# GBox2-can_diy.net
KiCad netlist of a schematic drawn in EAGLE
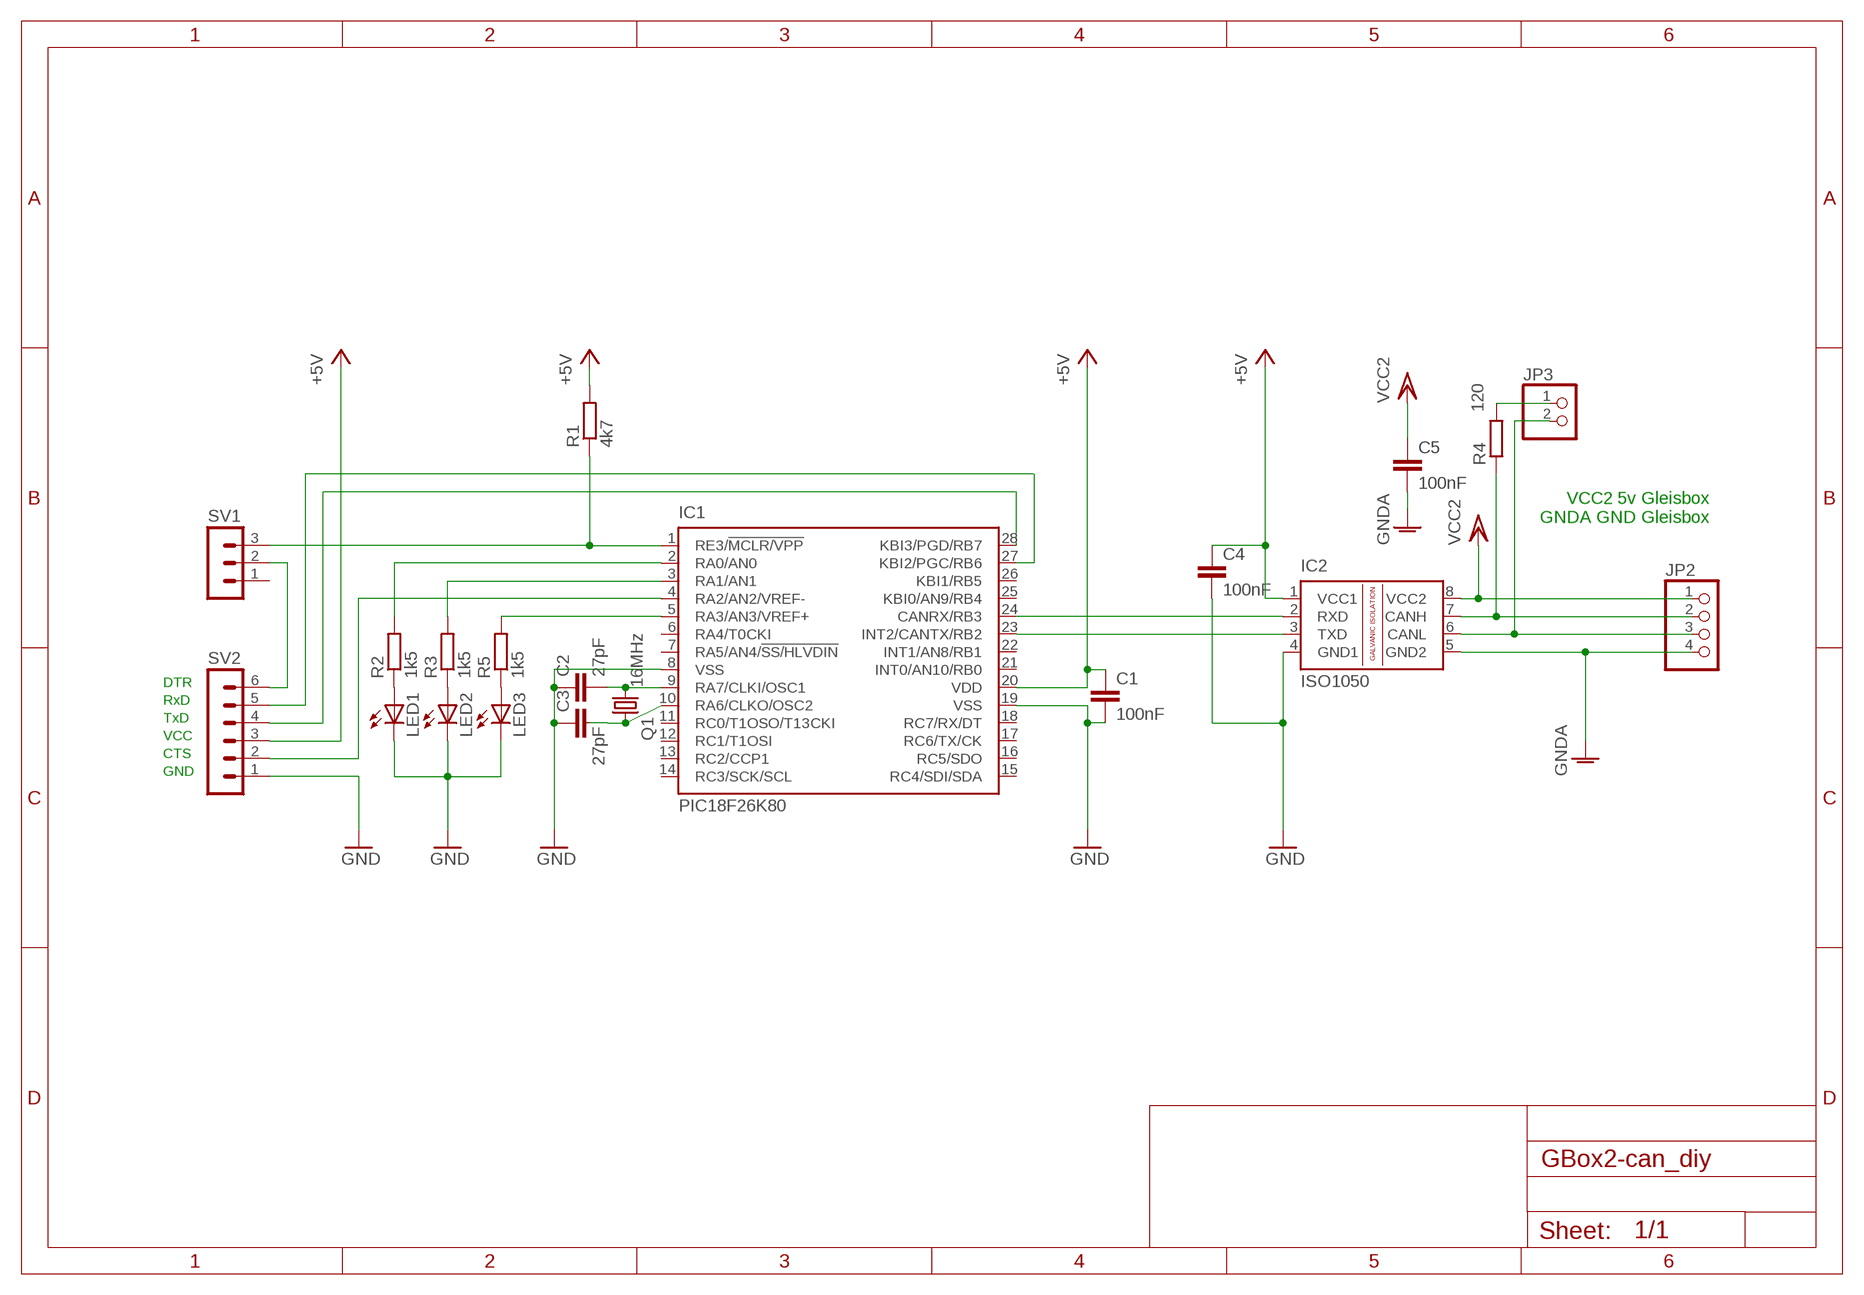
[diagram p0: schematic, sheet 1]

(export (version "E")
  (design (tool "Eeschema 10.0.6"))
  (components
    (comp (ref "C1")
      (value "100nF")
      (footprint "eagle-import:C1206")
      (libsource (lib "eagle-import") (part "C-EUC1206"))
    )
    (comp (ref "C2")
      (value "27pF")
      (footprint "eagle-import:C1206")
      (libsource (lib "eagle-import") (part "C-EUC1206"))
    )
    (comp (ref "C3")
      (value "27pF")
      (footprint "eagle-import:C1206")
      (libsource (lib "eagle-import") (part "C-EUC1206"))
    )
    (comp (ref "C4")
      (value "100nF")
      (footprint "eagle-import:C1206")
      (libsource (lib "eagle-import") (part "C-EUC1206"))
    )
    (comp (ref "C5")
      (value "100nF")
      (footprint "eagle-import:C1206")
      (libsource (lib "eagle-import") (part "C-EUC1206"))
    )
    (comp (ref "IC1")
      (value "PIC18F26K80")
      (footprint "eagle-import:SO28W")
      (libsource (lib "eagle-import") (part "PIC18F26K80-E/SO"))
    )
    (comp (ref "IC2")
      (value "ISO1050")
      (footprint "eagle-import:DUB-R-PDSO-G8")
      (fields (field (name "MPN") "ISO1050DUBR"))
      (libsource (lib "eagle-import") (part "ISO1050DUB"))
    )
    (comp (ref "JP2")
      (value "PINHD-1X4")
      (footprint "eagle-import:1X04")
      (libsource (lib "eagle-import") (part "PINHD-1X4"))
    )
    (comp (ref "JP3")
      (value "PINHD-1X2")
      (footprint "eagle-import:1X02")
      (libsource (lib "eagle-import") (part "PINHD-1X2"))
    )
    (comp (ref "LED1")
      (value "LEDSML1206")
      (footprint "eagle-import:SML1206")
      (libsource (lib "eagle-import") (part "LEDSML1206"))
    )
    (comp (ref "LED2")
      (value "LEDSML1206")
      (footprint "eagle-import:SML1206")
      (libsource (lib "eagle-import") (part "LEDSML1206"))
    )
    (comp (ref "LED3")
      (value "LEDSML1206")
      (footprint "eagle-import:SML1206")
      (libsource (lib "eagle-import") (part "LEDSML1206"))
    )
    (comp (ref "Q1")
      (value "16MHz")
      (footprint "eagle-import:HC49UP")
      (libsource (lib "eagle-import") (part "CRYSTALHC49UP"))
    )
    (comp (ref "R1")
      (value "4k7")
      (footprint "eagle-import:R1206")
      (libsource (lib "eagle-import") (part "R-EU_R1206"))
    )
    (comp (ref "R2")
      (value "1k5")
      (footprint "eagle-import:R1206")
      (libsource (lib "eagle-import") (part "R-EU_R1206"))
    )
    (comp (ref "R3")
      (value "1k5")
      (footprint "eagle-import:R1206")
      (libsource (lib "eagle-import") (part "R-EU_R1206"))
    )
    (comp (ref "R4")
      (value "120")
      (footprint "eagle-import:0204_7")
      (libsource (lib "eagle-import") (part "R-EU_0204/7"))
    )
    (comp (ref "R5")
      (value "1k5")
      (footprint "eagle-import:R1206")
      (libsource (lib "eagle-import") (part "R-EU_R1206"))
    )
    (comp (ref "SV1")
      (value "MA03-1")
      (footprint "eagle-import:MA03-1")
      (libsource (lib "eagle-import") (part "MA03-1"))
    )
    (comp (ref "SV2")
      (value "MA06-1")
      (footprint "eagle-import:MA06-1")
      (libsource (lib "eagle-import") (part "MA06-1"))
    )
  )
  (nets
    (net (code "1") (name "+5V") (class "Default")
      (node (ref "C1") (pin "1") (pinfunction "1_1") (pintype "passive"))
      (node (ref "C4") (pin "1") (pinfunction "1_1") (pintype "passive"))
      (node (ref "IC1") (pin "20") (pinfunction "VDD_20") (pintype "power_in"))
      (node (ref "IC2") (pin "1") (pinfunction "VCC1_1") (pintype "input"))
      (node (ref "R1") (pin "2") (pinfunction "2_2") (pintype "passive"))
      (node (ref "SV2") (pin "3") (pinfunction "3_3") (pintype "passive"))
    )
    (net (code "2") (name "GND") (class "Default")
      (node (ref "C1") (pin "2") (pinfunction "2_2") (pintype "passive"))
      (node (ref "C2") (pin "1") (pinfunction "1_1") (pintype "passive"))
      (node (ref "C3") (pin "1") (pinfunction "1_1") (pintype "passive"))
      (node (ref "C4") (pin "2") (pinfunction "2_2") (pintype "passive"))
      (node (ref "IC1") (pin "19") (pinfunction "VSS_19") (pintype "power_in"))
      (node (ref "IC1") (pin "8") (pinfunction "VSS_8") (pintype "power_in"))
      (node (ref "IC2") (pin "4") (pinfunction "GND1_4") (pintype "input"))
      (node (ref "LED1") (pin "C") (pinfunction "C_C") (pintype "passive"))
      (node (ref "LED2") (pin "C") (pinfunction "C_C") (pintype "passive"))
      (node (ref "LED3") (pin "C") (pinfunction "C_C") (pintype "passive"))
      (node (ref "SV2") (pin "1") (pinfunction "1_1") (pintype "passive"))
    )
    (net (code "3") (name "GNDA") (class "Default")
      (node (ref "C5") (pin "2") (pinfunction "2_2") (pintype "passive"))
      (node (ref "IC2") (pin "5") (pinfunction "GND2_5") (pintype "input"))
      (node (ref "JP2") (pin "4") (pinfunction "4_4") (pintype "passive"))
    )
    (net (code "4") (name "Net-(IC1-CANRX{slash}RB3)") (class "Default")
      (node (ref "IC1") (pin "24") (pinfunction "CANRX/RB3_24") (pintype "bidirectional"))
      (node (ref "IC2") (pin "2") (pinfunction "RXD_2") (pintype "input"))
    )
    (net (code "5") (name "Net-(IC1-INT2{slash}CANTX{slash}RB2)") (class "Default")
      (node (ref "IC1") (pin "23") (pinfunction "INT2/CANTX/RB2_23") (pintype "bidirectional"))
      (node (ref "IC2") (pin "3") (pinfunction "TXD_3") (pintype "input"))
    )
    (net (code "6") (name "Net-(IC1-KBI2{slash}PGC{slash}RB6)") (class "Default")
      (node (ref "IC1") (pin "27") (pinfunction "KBI2/PGC/RB6_27") (pintype "bidirectional"))
      (node (ref "SV2") (pin "5") (pinfunction "5_5") (pintype "passive"))
    )
    (net (code "7") (name "Net-(IC1-KBI3{slash}PGD{slash}RB7)") (class "Default")
      (node (ref "IC1") (pin "28") (pinfunction "KBI3/PGD/RB7_28") (pintype "bidirectional"))
      (node (ref "SV2") (pin "4") (pinfunction "4_4") (pintype "passive"))
    )
    (net (code "8") (name "Net-(IC1-RA0{slash}AN0)") (class "Default")
      (node (ref "IC1") (pin "2") (pinfunction "RA0/AN0_2") (pintype "bidirectional"))
      (node (ref "R2") (pin "2") (pinfunction "2_2") (pintype "passive"))
    )
    (net (code "9") (name "Net-(IC1-RA1{slash}AN1)") (class "Default")
      (node (ref "IC1") (pin "3") (pinfunction "RA1/AN1_3") (pintype "bidirectional"))
      (node (ref "R3") (pin "2") (pinfunction "2_2") (pintype "passive"))
    )
    (net (code "10") (name "Net-(IC1-RA2{slash}AN2{slash}VREF-)") (class "Default")
      (node (ref "IC1") (pin "4") (pinfunction "RA2/AN2/VREF-_4") (pintype "bidirectional"))
      (node (ref "SV2") (pin "2") (pinfunction "2_2") (pintype "passive"))
    )
    (net (code "11") (name "Net-(IC1-RA3{slash}AN3{slash}VREF+)") (class "Default")
      (node (ref "IC1") (pin "5") (pinfunction "RA3/AN3/VREF+_5") (pintype "bidirectional"))
      (node (ref "R5") (pin "2") (pinfunction "2_2") (pintype "passive"))
    )
    (net (code "12") (name "Net-(IC1-RA6{slash}CLKO{slash}OSC2)") (class "Default")
      (node (ref "C3") (pin "2") (pinfunction "2_2") (pintype "passive"))
      (node (ref "IC1") (pin "10") (pinfunction "RA6/CLKO/OSC2_10") (pintype "output"))
      (node (ref "Q1") (pin "1") (pinfunction "1_1") (pintype "passive"))
    )
    (net (code "13") (name "Net-(IC1-RA7{slash}CLKI{slash}OSC1)") (class "Default")
      (node (ref "C2") (pin "2") (pinfunction "2_2") (pintype "passive"))
      (node (ref "IC1") (pin "9") (pinfunction "RA7/CLKI/OSC1_9") (pintype "input"))
      (node (ref "Q1") (pin "2") (pinfunction "2_2") (pintype "passive"))
    )
    (net (code "14") (name "Net-(IC1-RE3{slash}~{MCLR{slash}VPP})") (class "Default")
      (node (ref "IC1") (pin "1") (pinfunction "RE3/~{MCLR/VPP}_1") (pintype "input"))
      (node (ref "R1") (pin "1") (pinfunction "1_1") (pintype "passive"))
      (node (ref "SV1") (pin "3") (pinfunction "3_3") (pintype "passive"))
    )
    (net (code "15") (name "Net-(IC2-CANH)") (class "Default")
      (node (ref "IC2") (pin "7") (pinfunction "CANH_7") (pintype "input"))
      (node (ref "JP2") (pin "2") (pinfunction "2_2") (pintype "passive"))
      (node (ref "R4") (pin "1") (pinfunction "1_1") (pintype "passive"))
    )
    (net (code "16") (name "Net-(IC2-CANL)") (class "Default")
      (node (ref "IC2") (pin "6") (pinfunction "CANL_6") (pintype "input"))
      (node (ref "JP2") (pin "3") (pinfunction "3_3") (pintype "passive"))
      (node (ref "JP3") (pin "2") (pinfunction "2_2") (pintype "passive"))
    )
    (net (code "17") (name "Net-(JP3-Pad1)") (class "Default")
      (node (ref "JP3") (pin "1") (pinfunction "1_1") (pintype "passive"))
      (node (ref "R4") (pin "2") (pinfunction "2_2") (pintype "passive"))
    )
    (net (code "18") (name "Net-(LED1-PadA)") (class "Default")
      (node (ref "LED1") (pin "A") (pinfunction "A_A") (pintype "passive"))
      (node (ref "R2") (pin "1") (pinfunction "1_1") (pintype "passive"))
    )
    (net (code "19") (name "Net-(LED2-PadA)") (class "Default")
      (node (ref "LED2") (pin "A") (pinfunction "A_A") (pintype "passive"))
      (node (ref "R3") (pin "1") (pinfunction "1_1") (pintype "passive"))
    )
    (net (code "20") (name "Net-(LED3-PadA)") (class "Default")
      (node (ref "LED3") (pin "A") (pinfunction "A_A") (pintype "passive"))
      (node (ref "R5") (pin "1") (pinfunction "1_1") (pintype "passive"))
    )
    (net (code "21") (name "Net-(SV1-Pad2)") (class "Default")
      (node (ref "SV1") (pin "2") (pinfunction "2_2") (pintype "passive"))
      (node (ref "SV2") (pin "6") (pinfunction "6_6") (pintype "passive"))
    )
    (net (code "22") (name "VCC2") (class "Default")
      (node (ref "C5") (pin "1") (pinfunction "1_1") (pintype "passive"))
      (node (ref "IC2") (pin "8") (pinfunction "VCC2_8") (pintype "input"))
      (node (ref "JP2") (pin "1") (pinfunction "1_1") (pintype "passive"))
    )
    (net (code "23") (name "unconnected-(IC1-INT0{slash}AN10{slash}RB0-Pad21)") (class "Default")
      (node (ref "IC1") (pin "21") (pinfunction "INT0/AN10/RB0_21") (pintype "bidirectional"))
    )
    (net (code "24") (name "unconnected-(IC1-INT1{slash}AN8{slash}RB1-Pad22)") (class "Default")
      (node (ref "IC1") (pin "22") (pinfunction "INT1/AN8/RB1_22") (pintype "bidirectional"))
    )
    (net (code "25") (name "unconnected-(IC1-KBI0{slash}AN9{slash}RB4-Pad25)") (class "Default")
      (node (ref "IC1") (pin "25") (pinfunction "KBI0/AN9/RB4_25") (pintype "bidirectional"))
    )
    (net (code "26") (name "unconnected-(IC1-KBI1{slash}RB5-Pad26)") (class "Default")
      (node (ref "IC1") (pin "26") (pinfunction "KBI1/RB5_26") (pintype "bidirectional"))
    )
    (net (code "27") (name "unconnected-(IC1-RA4{slash}T0CKI-Pad6)") (class "Default")
      (node (ref "IC1") (pin "6") (pinfunction "RA4/T0CKI_6") (pintype "bidirectional"))
    )
    (net (code "28") (name "unconnected-(IC1-RA5{slash}AN4{slash}~{SS{slash}HLVDIN}-Pad7)") (class "Default")
      (node (ref "IC1") (pin "7") (pinfunction "RA5/AN4/~{SS/HLVDIN}_7") (pintype "bidirectional"))
    )
    (net (code "29") (name "unconnected-(IC1-RC0{slash}T1OSO{slash}T13CKI-Pad11)") (class "Default")
      (node (ref "IC1") (pin "11") (pinfunction "RC0/T1OSO/T13CKI_11") (pintype "bidirectional"))
    )
    (net (code "30") (name "unconnected-(IC1-RC1{slash}T1OSI-Pad12)") (class "Default")
      (node (ref "IC1") (pin "12") (pinfunction "RC1/T1OSI_12") (pintype "bidirectional"))
    )
    (net (code "31") (name "unconnected-(IC1-RC2{slash}CCP1-Pad13)") (class "Default")
      (node (ref "IC1") (pin "13") (pinfunction "RC2/CCP1_13") (pintype "bidirectional"))
    )
    (net (code "32") (name "unconnected-(IC1-RC3{slash}SCK{slash}SCL-Pad14)") (class "Default")
      (node (ref "IC1") (pin "14") (pinfunction "RC3/SCK/SCL_14") (pintype "bidirectional"))
    )
    (net (code "33") (name "unconnected-(IC1-RC4{slash}SDI{slash}SDA-Pad15)") (class "Default")
      (node (ref "IC1") (pin "15") (pinfunction "RC4/SDI/SDA_15") (pintype "bidirectional"))
    )
    (net (code "34") (name "unconnected-(IC1-RC5{slash}SDO-Pad16)") (class "Default")
      (node (ref "IC1") (pin "16") (pinfunction "RC5/SDO_16") (pintype "bidirectional"))
    )
    (net (code "35") (name "unconnected-(IC1-RC6{slash}TX{slash}CK-Pad17)") (class "Default")
      (node (ref "IC1") (pin "17") (pinfunction "RC6/TX/CK_17") (pintype "bidirectional"))
    )
    (net (code "36") (name "unconnected-(IC1-RC7{slash}RX{slash}DT-Pad18)") (class "Default")
      (node (ref "IC1") (pin "18") (pinfunction "RC7/RX/DT_18") (pintype "bidirectional"))
    )
    (net (code "37") (name "unconnected-(SV1-Pad1)") (class "Default")
      (node (ref "SV1") (pin "1") (pinfunction "1_1") (pintype "passive"))
    )
  )
)
